# OmniCar_v0_1.net
KiCad netlist of a schematic drawn in EAGLE
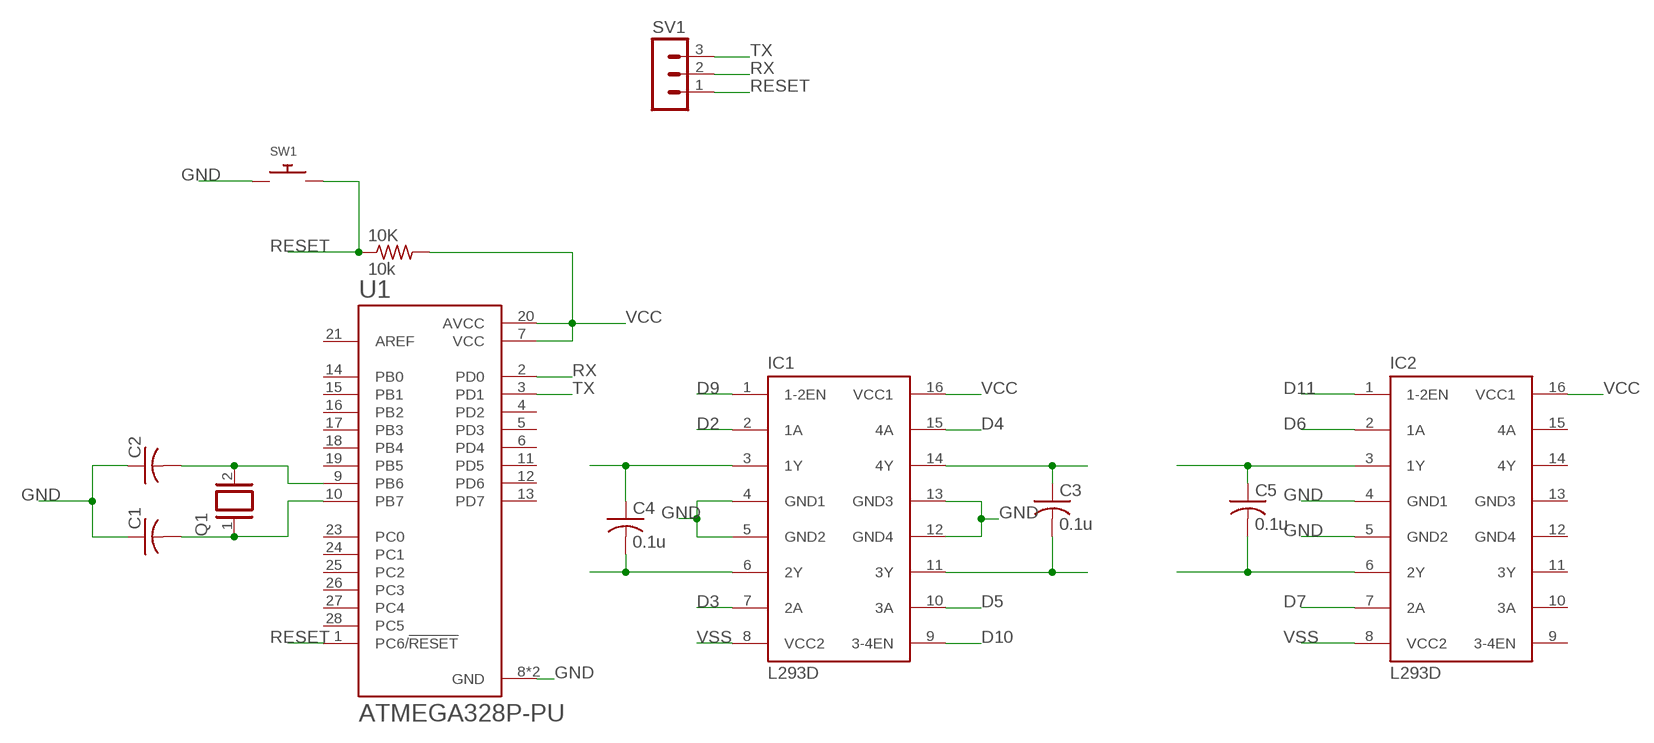
[diagram p0: schematic, sheet 1]

(export (version "E")
  (design (tool "Eeschema 10.0.6"))
  (components
    (comp (ref "10K")
      (value "10k")
      (footprint "eagle-import:0204_5")
      (libsource (lib "eagle-import") (part "R-US_0204/5"))
    )
    (comp (ref "C1")
      (value "C-US025-030X050")
      (footprint "eagle-import:C025-030X050")
      (libsource (lib "eagle-import") (part "C-US025-030X050"))
    )
    (comp (ref "C2")
      (value "C-US025-030X050")
      (footprint "eagle-import:C025-030X050")
      (libsource (lib "eagle-import") (part "C-US025-030X050"))
    )
    (comp (ref "C3")
      (value "0.1u")
      (footprint "eagle-import:C025-030X050")
      (libsource (lib "eagle-import") (part "C-US025-030X050"))
    )
    (comp (ref "C4")
      (value "0.1u")
      (footprint "eagle-import:C025-030X050")
      (libsource (lib "eagle-import") (part "C-US025-030X050"))
    )
    (comp (ref "C5")
      (value "0.1u")
      (footprint "eagle-import:C025-030X050")
      (libsource (lib "eagle-import") (part "C-US025-030X050"))
    )
    (comp (ref "IC1")
      (value "L293D")
      (footprint "eagle-import:DIL16")
      (fields (field (name "MF") "STMicroelectronics"))
      (libsource (lib "eagle-import") (part "L293D"))
    )
    (comp (ref "IC2")
      (value "L293D")
      (footprint "eagle-import:DIL16")
      (fields (field (name "MF") "STMicroelectronics"))
      (libsource (lib "eagle-import") (part "L293D"))
    )
    (comp (ref "Q1")
      (value "XTAL")
      (footprint "eagle-import:Q")
      (libsource (lib "eagle-import") (part "XTAL"))
    )
    (comp (ref "SV1")
      (value "MA03-1")
      (footprint "eagle-import:MA03-1")
      (libsource (lib "eagle-import") (part "MA03-1"))
    )
    (comp (ref "SW1")
      (value "SWITCH_PUSHBUTTONEVQ-PE")
      (footprint "eagle-import:TACT_PANA-EVQ")
      (libsource (lib "eagle-import") (part "SWITCH_PUSHBUTTONEVQ-PE"))
    )
    (comp (ref "U1")
      (value "ATMEGA328P-PU")
      (footprint "eagle-import:DIP794W46P254L2967H457Q28B")
      (fields (field (name "MF") "Microchip"))
      (libsource (lib "eagle-import") (part "ATMEGA328P-PU"))
    )
  )
  (nets
    (net (code "1") (name "/D2") (class "Default")
      (node (ref "IC1") (pin "2") (pinfunction "1A_2") (pintype "input"))
    )
    (net (code "2") (name "/D3") (class "Default")
      (node (ref "IC1") (pin "7") (pinfunction "2A_7") (pintype "input"))
    )
    (net (code "3") (name "/D4") (class "Default")
      (node (ref "IC1") (pin "15") (pinfunction "4A_15") (pintype "input"))
    )
    (net (code "4") (name "/D5") (class "Default")
      (node (ref "IC1") (pin "10") (pinfunction "3A_10") (pintype "input"))
    )
    (net (code "5") (name "/D6") (class "Default")
      (node (ref "IC2") (pin "2") (pinfunction "1A_2") (pintype "input"))
    )
    (net (code "6") (name "/D7") (class "Default")
      (node (ref "IC2") (pin "7") (pinfunction "2A_7") (pintype "input"))
    )
    (net (code "7") (name "/D9") (class "Default")
      (node (ref "IC1") (pin "1") (pinfunction "1-2EN_1") (pintype "input"))
    )
    (net (code "8") (name "/D10") (class "Default")
      (node (ref "IC1") (pin "9") (pinfunction "3-4EN_9") (pintype "input"))
    )
    (net (code "9") (name "/D11") (class "Default")
      (node (ref "IC2") (pin "1") (pinfunction "1-2EN_1") (pintype "input"))
    )
    (net (code "10") (name "/GND") (class "Default")
      (node (ref "C1") (pin "1") (pinfunction "1_1") (pintype "passive"))
      (node (ref "C2") (pin "1") (pinfunction "1_1") (pintype "passive"))
      (node (ref "IC1") (pin "12") (pinfunction "GND4_12") (pintype "power_in"))
      (node (ref "IC1") (pin "13") (pinfunction "GND3_13") (pintype "power_in"))
      (node (ref "IC1") (pin "4") (pinfunction "GND1_4") (pintype "power_in"))
      (node (ref "IC1") (pin "5") (pinfunction "GND2_5") (pintype "power_in"))
      (node (ref "IC2") (pin "4") (pinfunction "GND1_4") (pintype "power_in"))
      (node (ref "IC2") (pin "5") (pinfunction "GND2_5") (pintype "power_in"))
      (node (ref "SW1") (pin "P$1") (pinfunction "P$1_P$1") (pintype "passive"))
      (node (ref "U1") (pin "22") (pinfunction "GND_22") (pintype "power_in"))
      (node (ref "U1") (pin "8") (pinfunction "GND_8") (pintype "power_in"))
    )
    (net (code "11") (name "/GND3") (class "Default")
      (node (ref "IC2") (pin "13") (pinfunction "GND3_13") (pintype "power_in"))
    )
    (net (code "12") (name "/GND4") (class "Default")
      (node (ref "IC2") (pin "12") (pinfunction "GND4_12") (pintype "power_in"))
    )
    (net (code "13") (name "/RESET") (class "Default")
      (node (ref "10K") (pin "1") (pinfunction "1_1") (pintype "passive"))
      (node (ref "SV1") (pin "1") (pinfunction "1_1") (pintype "passive"))
      (node (ref "SW1") (pin "P$2") (pinfunction "P$2_P$2") (pintype "passive"))
      (node (ref "U1") (pin "1") (pinfunction "PC6/~{RESET}_1") (pintype "bidirectional"))
    )
    (net (code "14") (name "/RX") (class "Default")
      (node (ref "SV1") (pin "2") (pinfunction "2_2") (pintype "passive"))
      (node (ref "U1") (pin "2") (pinfunction "PD0_2") (pintype "bidirectional"))
    )
    (net (code "15") (name "/TX") (class "Default")
      (node (ref "SV1") (pin "3") (pinfunction "3_3") (pintype "passive"))
      (node (ref "U1") (pin "3") (pinfunction "PD1_3") (pintype "bidirectional"))
    )
    (net (code "16") (name "/VCC") (class "Default")
      (node (ref "10K") (pin "2") (pinfunction "2_2") (pintype "passive"))
      (node (ref "IC1") (pin "16") (pinfunction "VCC1_16") (pintype "power_in"))
      (node (ref "IC2") (pin "16") (pinfunction "VCC1_16") (pintype "power_in"))
      (node (ref "U1") (pin "20") (pinfunction "AVCC_20") (pintype "power_in"))
      (node (ref "U1") (pin "7") (pinfunction "VCC_7") (pintype "power_in"))
    )
    (net (code "17") (name "/VSS") (class "Default")
      (node (ref "IC1") (pin "8") (pinfunction "VCC2_8") (pintype "power_in"))
      (node (ref "IC2") (pin "8") (pinfunction "VCC2_8") (pintype "power_in"))
    )
    (net (code "18") (name "Net-(IC1-1Y)") (class "Default")
      (node (ref "C4") (pin "1") (pinfunction "1_1") (pintype "passive"))
      (node (ref "IC1") (pin "3") (pinfunction "1Y_3") (pintype "output"))
    )
    (net (code "19") (name "Net-(IC1-2Y)") (class "Default")
      (node (ref "C4") (pin "2") (pinfunction "2_2") (pintype "passive"))
      (node (ref "IC1") (pin "6") (pinfunction "2Y_6") (pintype "output"))
    )
    (net (code "20") (name "Net-(IC1-3Y)") (class "Default")
      (node (ref "C3") (pin "2") (pinfunction "2_2") (pintype "passive"))
      (node (ref "IC1") (pin "11") (pinfunction "3Y_11") (pintype "output"))
    )
    (net (code "21") (name "Net-(IC1-4Y)") (class "Default")
      (node (ref "C3") (pin "1") (pinfunction "1_1") (pintype "passive"))
      (node (ref "IC1") (pin "14") (pinfunction "4Y_14") (pintype "output"))
    )
    (net (code "22") (name "Net-(IC2-1Y)") (class "Default")
      (node (ref "C5") (pin "1") (pinfunction "1_1") (pintype "passive"))
      (node (ref "IC2") (pin "3") (pinfunction "1Y_3") (pintype "output"))
    )
    (net (code "23") (name "Net-(IC2-2Y)") (class "Default")
      (node (ref "C5") (pin "2") (pinfunction "2_2") (pintype "passive"))
      (node (ref "IC2") (pin "6") (pinfunction "2Y_6") (pintype "output"))
    )
    (net (code "24") (name "Net-(U1-PB6)") (class "Default")
      (node (ref "C2") (pin "2") (pinfunction "2_2") (pintype "passive"))
      (node (ref "Q1") (pin "2") (pinfunction "2_2") (pintype "passive"))
      (node (ref "U1") (pin "9") (pinfunction "PB6_9") (pintype "bidirectional"))
    )
    (net (code "25") (name "Net-(U1-PB7)") (class "Default")
      (node (ref "C1") (pin "2") (pinfunction "2_2") (pintype "passive"))
      (node (ref "Q1") (pin "1") (pinfunction "1_1") (pintype "passive"))
      (node (ref "U1") (pin "10") (pinfunction "PB7_10") (pintype "bidirectional"))
    )
    (net (code "26") (name "unconnected-(IC2-3-4EN-Pad9)") (class "Default")
      (node (ref "IC2") (pin "9") (pinfunction "3-4EN_9") (pintype "input"))
    )
    (net (code "27") (name "unconnected-(IC2-3A-Pad10)") (class "Default")
      (node (ref "IC2") (pin "10") (pinfunction "3A_10") (pintype "input"))
    )
    (net (code "28") (name "unconnected-(IC2-3Y-Pad11)") (class "Default")
      (node (ref "IC2") (pin "11") (pinfunction "3Y_11") (pintype "output"))
    )
    (net (code "29") (name "unconnected-(IC2-4A-Pad15)") (class "Default")
      (node (ref "IC2") (pin "15") (pinfunction "4A_15") (pintype "input"))
    )
    (net (code "30") (name "unconnected-(IC2-4Y-Pad14)") (class "Default")
      (node (ref "IC2") (pin "14") (pinfunction "4Y_14") (pintype "output"))
    )
    (net (code "31") (name "unconnected-(U1-AREF-Pad21)") (class "Default")
      (node (ref "U1") (pin "21") (pinfunction "AREF_21") (pintype "input"))
    )
    (net (code "32") (name "unconnected-(U1-PB0-Pad14)") (class "Default")
      (node (ref "U1") (pin "14") (pinfunction "PB0_14") (pintype "bidirectional"))
    )
    (net (code "33") (name "unconnected-(U1-PB1-Pad15)") (class "Default")
      (node (ref "U1") (pin "15") (pinfunction "PB1_15") (pintype "bidirectional"))
    )
    (net (code "34") (name "unconnected-(U1-PB2-Pad16)") (class "Default")
      (node (ref "U1") (pin "16") (pinfunction "PB2_16") (pintype "bidirectional"))
    )
    (net (code "35") (name "unconnected-(U1-PB3-Pad17)") (class "Default")
      (node (ref "U1") (pin "17") (pinfunction "PB3_17") (pintype "bidirectional"))
    )
    (net (code "36") (name "unconnected-(U1-PB4-Pad18)") (class "Default")
      (node (ref "U1") (pin "18") (pinfunction "PB4_18") (pintype "bidirectional"))
    )
    (net (code "37") (name "unconnected-(U1-PB5-Pad19)") (class "Default")
      (node (ref "U1") (pin "19") (pinfunction "PB5_19") (pintype "bidirectional"))
    )
    (net (code "38") (name "unconnected-(U1-PC0-Pad23)") (class "Default")
      (node (ref "U1") (pin "23") (pinfunction "PC0_23") (pintype "bidirectional"))
    )
    (net (code "39") (name "unconnected-(U1-PC1-Pad24)") (class "Default")
      (node (ref "U1") (pin "24") (pinfunction "PC1_24") (pintype "bidirectional"))
    )
    (net (code "40") (name "unconnected-(U1-PC2-Pad25)") (class "Default")
      (node (ref "U1") (pin "25") (pinfunction "PC2_25") (pintype "bidirectional"))
    )
    (net (code "41") (name "unconnected-(U1-PC3-Pad26)") (class "Default")
      (node (ref "U1") (pin "26") (pinfunction "PC3_26") (pintype "bidirectional"))
    )
    (net (code "42") (name "unconnected-(U1-PC4-Pad27)") (class "Default")
      (node (ref "U1") (pin "27") (pinfunction "PC4_27") (pintype "bidirectional"))
    )
    (net (code "43") (name "unconnected-(U1-PC5-Pad28)") (class "Default")
      (node (ref "U1") (pin "28") (pinfunction "PC5_28") (pintype "bidirectional"))
    )
    (net (code "44") (name "unconnected-(U1-PD2-Pad4)") (class "Default")
      (node (ref "U1") (pin "4") (pinfunction "PD2_4") (pintype "bidirectional"))
    )
    (net (code "45") (name "unconnected-(U1-PD3-Pad5)") (class "Default")
      (node (ref "U1") (pin "5") (pinfunction "PD3_5") (pintype "bidirectional"))
    )
    (net (code "46") (name "unconnected-(U1-PD4-Pad6)") (class "Default")
      (node (ref "U1") (pin "6") (pinfunction "PD4_6") (pintype "bidirectional"))
    )
    (net (code "47") (name "unconnected-(U1-PD5-Pad11)") (class "Default")
      (node (ref "U1") (pin "11") (pinfunction "PD5_11") (pintype "bidirectional"))
    )
    (net (code "48") (name "unconnected-(U1-PD6-Pad12)") (class "Default")
      (node (ref "U1") (pin "12") (pinfunction "PD6_12") (pintype "bidirectional"))
    )
    (net (code "49") (name "unconnected-(U1-PD7-Pad13)") (class "Default")
      (node (ref "U1") (pin "13") (pinfunction "PD7_13") (pintype "bidirectional"))
    )
  )
)
